# Power.net
KiCad netlist of a schematic drawn in Altium Designer
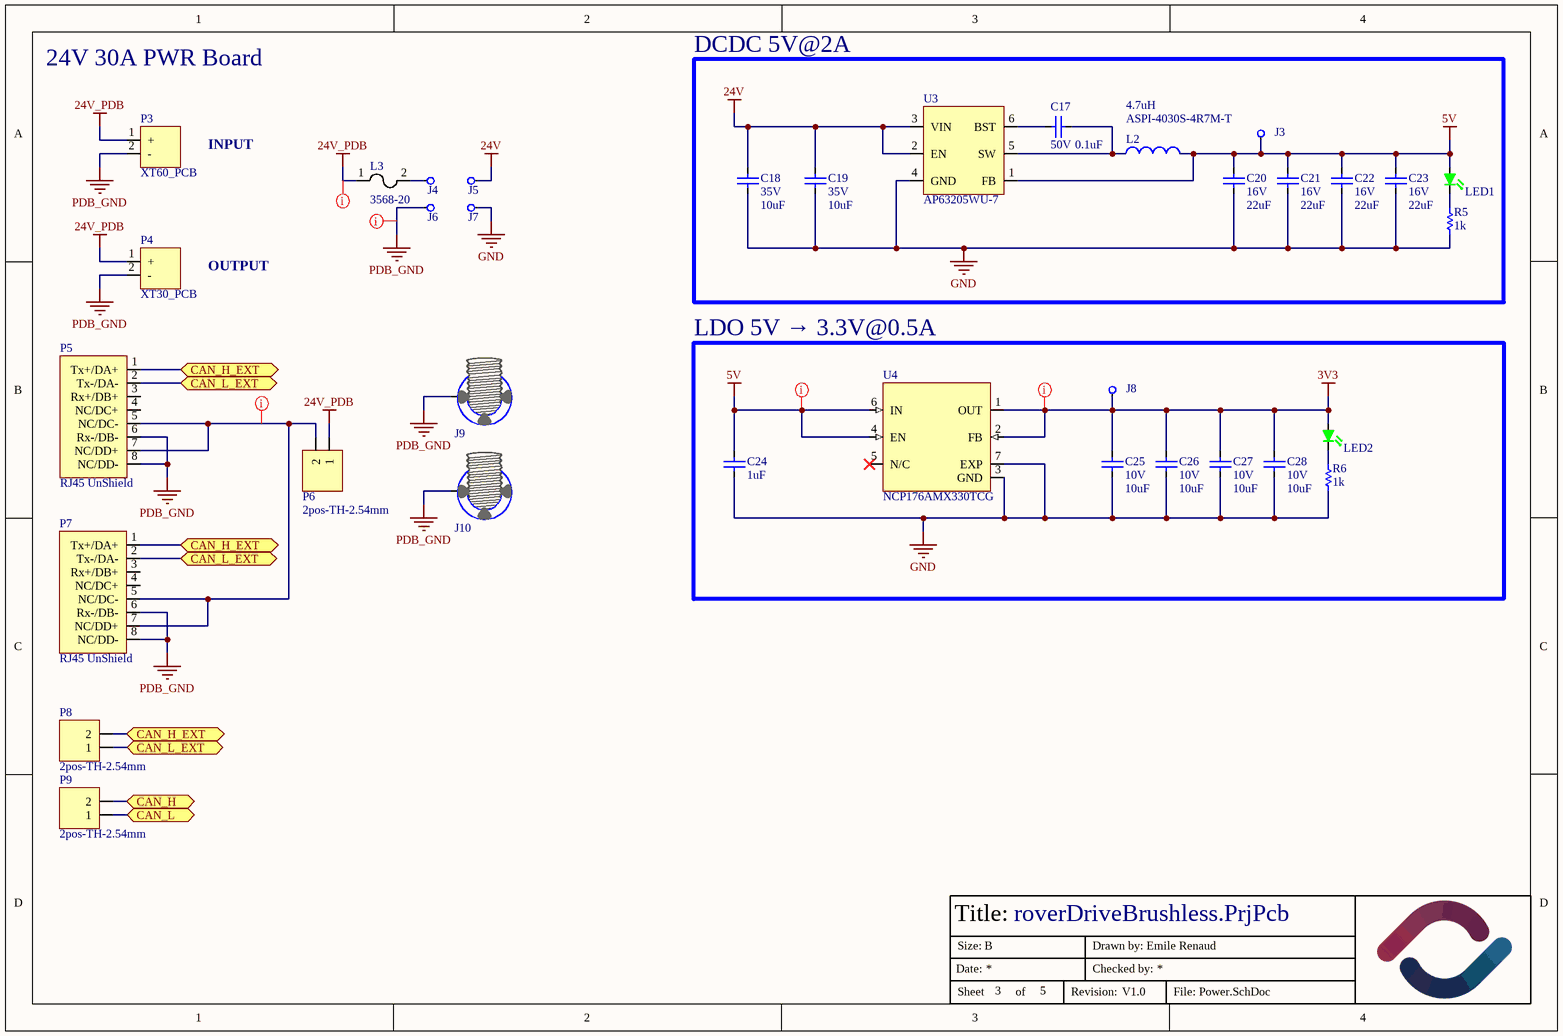
[diagram p0: Power.SchDoc]

(export (version "E")
  (design (tool "Eeschema 10.0.6"))
  (components
    (comp (ref "C17")
      (value "0.1uF")
      (footprint "CAPACITOR-0603")
      (description "Capacitor-0603-0.1uF-50V-X7R")
      (fields (field (name "VOLT") "50V"))
      (libsource (lib "Capacitors") (part "Capacitor-0603-0.1uF-50V-X7R"))
    )
    (comp (ref "C18")
      (value "10uF")
      (footprint "CAPACITOR-0805")
      (description "Capacitor-0805-10uF-35V-X5R")
      (fields (field (name "VOLT") "35V"))
      (libsource (lib "Capacitors") (part "Capacitor-0805-10uF-35V-X5R"))
    )
    (comp (ref "C19")
      (value "10uF")
      (footprint "CAPACITOR-0805")
      (description "Capacitor-0805-10uF-35V-X5R")
      (fields (field (name "VOLT") "35V"))
      (libsource (lib "Capacitors") (part "Capacitor-0805-10uF-35V-X5R"))
    )
    (comp (ref "C20")
      (value "22uF")
      (footprint "CAPACITOR-0805")
      (description "Capacitor-0805-22uF-16V-X5R")
      (fields (field (name "VOLT") "16V"))
      (libsource (lib "Capacitors") (part "Capacitor-0805-22uF-16V-X5R"))
    )
    (comp (ref "C21")
      (value "22uF")
      (footprint "CAPACITOR-0805")
      (description "Capacitor-0805-22uF-16V-X5R")
      (fields (field (name "VOLT") "16V"))
      (libsource (lib "Capacitors") (part "Capacitor-0805-22uF-16V-X5R"))
    )
    (comp (ref "C22")
      (value "22uF")
      (footprint "CAPACITOR-0805")
      (description "Capacitor-0805-22uF-16V-X5R")
      (fields (field (name "VOLT") "16V"))
      (libsource (lib "Capacitors") (part "Capacitor-0805-22uF-16V-X5R"))
    )
    (comp (ref "C23")
      (value "22uF")
      (footprint "CAPACITOR-0805")
      (description "Capacitor-0805-22uF-16V-X5R")
      (fields (field (name "VOLT") "16V"))
      (libsource (lib "Capacitors") (part "Capacitor-0805-22uF-16V-X5R"))
    )
    (comp (ref "C24")
      (value "1uF")
      (footprint "CAPACITOR-0603")
      (description "Capacitor-0603-1uF-25V-X5R")
      (libsource (lib "Capacitors") (part "Capacitor-0603-1uF-25V-X5R"))
    )
    (comp (ref "C25")
      (value "10uF")
      (footprint "CAPACITOR-0603")
      (description "10 µF ±20% 10V Ceramic Capacitor X5R 0603 (1608 Metric)")
      (fields (field (name "VOLT") "10V") (field (name "Comment") "Capacitor-0603-10uF-10V-X5R"))
      (libsource (lib "Capacitors") (part "Capacitor-0603-10uF-10V-X5R"))
    )
    (comp (ref "C26")
      (value "10uF")
      (footprint "CAPACITOR-0603")
      (description "10 µF ±20% 10V Ceramic Capacitor X5R 0603 (1608 Metric)")
      (fields (field (name "VOLT") "10V") (field (name "Comment") "Capacitor-0603-10uF-10V-X5R"))
      (libsource (lib "Capacitors") (part "Capacitor-0603-10uF-10V-X5R"))
    )
    (comp (ref "C27")
      (value "10uF")
      (footprint "CAPACITOR-0603")
      (description "10 µF ±20% 10V Ceramic Capacitor X5R 0603 (1608 Metric)")
      (fields (field (name "VOLT") "10V") (field (name "Comment") "Capacitor-0603-10uF-10V-X5R"))
      (libsource (lib "Capacitors") (part "Capacitor-0603-10uF-10V-X5R"))
    )
    (comp (ref "C28")
      (value "10uF")
      (footprint "CAPACITOR-0603")
      (description "10 µF ±20% 10V Ceramic Capacitor X5R 0603 (1608 Metric)")
      (fields (field (name "VOLT") "10V") (field (name "Comment") "Capacitor-0603-10uF-10V-X5R"))
      (libsource (lib "Capacitors") (part "Capacitor-0603-10uF-10V-X5R"))
    )
    (comp (ref "J3")
      (value "hole")
      (footprint "PAD-1.2MM-silk")
      (libsource (lib "JumpersAndHoles") (part "PAD 1.2mm"))
    )
    (comp (ref "J4")
      (value "hole")
      (footprint "HOLE-2.70MM")
      (description "Hole for 12 AWG Stranded Wire")
      (libsource (lib "JumpersAndHoles") (part "Hole 2.70mm AWG12-Stranded"))
    )
    (comp (ref "J5")
      (value "hole")
      (footprint "HOLE-2.70MM")
      (description "Hole for 12 AWG Stranded Wire")
      (libsource (lib "JumpersAndHoles") (part "Hole 2.70mm AWG12-Stranded"))
    )
    (comp (ref "J6")
      (value "hole")
      (footprint "HOLE-2.70MM")
      (description "Hole for 12 AWG Stranded Wire")
      (libsource (lib "JumpersAndHoles") (part "Hole 2.70mm AWG12-Stranded"))
    )
    (comp (ref "J7")
      (value "hole")
      (footprint "HOLE-2.70MM")
      (description "Hole for 12 AWG Stranded Wire")
      (libsource (lib "JumpersAndHoles") (part "Hole 2.70mm AWG12-Stranded"))
    )
    (comp (ref "J8")
      (value "hole")
      (footprint "PAD-1.2MM-silk")
      (libsource (lib "JumpersAndHoles") (part "PAD 1.2mm"))
    )
    (comp (ref "J9")
      (value "hole")
      (footprint "HOLE-3.40MM-M3-7MMEYELET-MountingFeature")
      (description "Hole for M3 Bolt with 7mm pad")
      (libsource (lib "JumpersAndHoles") (part "Hole 3.40mm M3-MountingFeature"))
    )
    (comp (ref "J10")
      (value "hole")
      (footprint "HOLE-3.40MM-M3-7MMEYELET-MountingFeature")
      (description "Hole for M3 Bolt with 7mm pad")
      (libsource (lib "JumpersAndHoles") (part "Hole 3.40mm M3-MountingFeature"))
    )
    (comp (ref "L2")
      (value "ASPI-4030S-4R7M-T")
      (footprint "INDUCTOR_ASPI-4030S-100M")
      (description "4.7 µH Shielded Drum Core, Wirewound Inductor 2 A 60mOhm Nonstandard")
      (fields (field (name "ALTIUM_VALUE") "4.7uH"))
      (libsource (lib "Inductors") (part "ASPI-4030S-4R7M-T"))
    )
    (comp (ref "L3")
      (value "3568-20")
      (footprint "FUSE_3568-20")
      (description "Fuse Holder 30 A 500V 1 Circuit Blade Through Hole")
      (libsource (lib "Fuses") (part "3568-20"))
    )
    (comp (ref "LED1")
      (value "3147-B1911NG--20D000214U1930CT-ND")
      (footprint "LED-0603-2PIN-SILKSCREEN")
      (description "LED GREEN DIFFUSED 0603 SMD")
      (libsource (lib "LEDs") (part "LED_GREEN"))
    )
    (comp (ref "LED2")
      (value "3147-B1911NG--20D000214U1930CT-ND")
      (footprint "LED-0603-2PIN-SILKSCREEN")
      (description "LED GREEN DIFFUSED 0603 SMD")
      (libsource (lib "LEDs") (part "LED_GREEN"))
    )
    (comp (ref "P3")
      (value "XT60_PCB")
      (footprint "XT60PW-M")
      (description "XT60")
      (libsource (lib "BatteriesConnector") (part "XT60_pcb"))
    )
    (comp (ref "P4")
      (value "XT30_PCB")
      (footprint "XT30PW_smd")
      (description "XT30")
      (libsource (lib "BatteriesConnector") (part "XT30_pcb"))
    )
    (comp (ref "P5")
      (value "RJ45 UnShield")
      (footprint "AMPHENOL_54602-908LF")
      (description "Jack Modular Connector 8p8c (RJ45, Ethernet) 90° Angle (Right) Unshielded Cat3")
      (libsource (lib "PC-connector") (part "RJ545"))
    )
    (comp (ref "P6")
      (value "2pos-TH-2.54mm")
      (footprint "HDR1X2")
      (description "2pos TH 2.54mm Header")
      (libsource (lib "") (part "2pos-TH-2.54mm_1"))
    )
    (comp (ref "P7")
      (value "RJ45 UnShield")
      (footprint "AMPHENOL_54602-908LF")
      (description "Jack Modular Connector 8p8c (RJ45, Ethernet) 90° Angle (Right) Unshielded Cat3")
      (libsource (lib "PC-connector") (part "RJ545"))
    )
    (comp (ref "P8")
      (value "2pos-TH-2.54mm")
      (footprint "HDR1X2")
      (description "2pos TH 2.54mm Header")
      (libsource (lib "Header") (part "2pos-TH-2.54mm"))
    )
    (comp (ref "P9")
      (value "2pos-TH-2.54mm")
      (footprint "HDR1X2")
      (description "2pos TH 2.54mm Header")
      (libsource (lib "Header") (part "2pos-TH-2.54mm"))
    )
    (comp (ref "R5")
      (value "1k")
      (footprint "Resistor-0603")
      (description "Resistor0603-1k")
      (fields (field (name "Comment") "SMT resistor"))
      (libsource (lib "Resistors") (part "Resistor0603-1k"))
    )
    (comp (ref "R6")
      (value "1k")
      (footprint "Resistor-0603")
      (description "Resistor0603-1k")
      (fields (field (name "Comment") "SMT resistor"))
      (libsource (lib "Resistors") (part "Resistor0603-1k"))
    )
    (comp (ref "U3")
      (value "AP63205WU-7")
      (footprint "SOT-23-6")
      (description "Fixed 5V@2A. 32V Input. SOT-23-6")
      (libsource (lib "PMIC-VoltageRegulators-DCDCSwitchingRegulators") (part "AP63205WU-7"))
    )
    (comp (ref "U4")
      (value "NCP176AMX330TCG")
      (footprint "PCB_Footprints:XFDFN-6 Exposed Pad")
      (description "IC REG LINEAR 3.3V 500mA 6-XDFN")
      (libsource (lib "PMIC-VoltageRegulators-LinearRegulators") (part "NCP176AMX330TCG"))
    )
  )
  (nets
    (net (code "1") (name "/CAN_H") (class "Default")
      (node (ref "P9") (pin "2") (pinfunction "2_2") (pintype "passive"))
    )
    (net (code "2") (name "/CAN_H_EXT") (class "Default")
      (node (ref "P5") (pin "1") (pinfunction "Tx+/DA+_1") (pintype "passive"))
      (node (ref "P7") (pin "1") (pinfunction "Tx+/DA+_1") (pintype "passive"))
      (node (ref "P8") (pin "2") (pinfunction "2_2") (pintype "passive"))
    )
    (net (code "3") (name "/CAN_L") (class "Default")
      (node (ref "P9") (pin "1") (pinfunction "1_1") (pintype "passive"))
    )
    (net (code "4") (name "/CAN_L_EXT") (class "Default")
      (node (ref "P5") (pin "2") (pinfunction "Tx-/DA-_2") (pintype "passive"))
      (node (ref "P7") (pin "2") (pinfunction "Tx-/DA-_2") (pintype "passive"))
      (node (ref "P8") (pin "1") (pinfunction "1_1") (pintype "passive"))
    )
    (net (code "5") (name "3V3") (class "Default")
      (node (ref "C25") (pin "2") (pinfunction "2_2") (pintype "passive"))
      (node (ref "C26") (pin "2") (pinfunction "2_2") (pintype "passive"))
      (node (ref "C27") (pin "2") (pinfunction "2_2") (pintype "passive"))
      (node (ref "C28") (pin "2") (pinfunction "2_2") (pintype "passive"))
      (node (ref "J8") (pin "1") (pinfunction "1_1") (pintype "passive"))
      (node (ref "LED2") (pin "2") (pinfunction "R_2") (pintype "passive"))
      (node (ref "U4") (pin "1") (pinfunction "OUT_1") (pintype "passive"))
      (node (ref "U4") (pin "2") (pinfunction "FB_2") (pintype "input"))
    )
    (net (code "6") (name "5V") (class "Default")
      (node (ref "C20") (pin "2") (pinfunction "2_2") (pintype "passive"))
      (node (ref "C21") (pin "2") (pinfunction "2_2") (pintype "passive"))
      (node (ref "C22") (pin "2") (pinfunction "2_2") (pintype "passive"))
      (node (ref "C23") (pin "2") (pinfunction "2_2") (pintype "passive"))
      (node (ref "C24") (pin "2") (pinfunction "2_2") (pintype "passive"))
      (node (ref "J3") (pin "1") (pinfunction "1_1") (pintype "passive"))
      (node (ref "L2") (pin "2") (pinfunction "2_2") (pintype "passive"))
      (node (ref "LED1") (pin "2") (pinfunction "R_2") (pintype "passive"))
      (node (ref "U3") (pin "1") (pinfunction "FB_1") (pintype "passive"))
      (node (ref "U4") (pin "4") (pinfunction "EN_4") (pintype "input"))
      (node (ref "U4") (pin "6") (pinfunction "IN_6") (pintype "input"))
    )
    (net (code "7") (name "24V") (class "Default")
      (node (ref "C18") (pin "2") (pinfunction "2_2") (pintype "passive"))
      (node (ref "C19") (pin "2") (pinfunction "2_2") (pintype "passive"))
      (node (ref "J5") (pin "1") (pinfunction "1_1") (pintype "passive"))
      (node (ref "U3") (pin "2") (pinfunction "EN_2") (pintype "passive"))
      (node (ref "U3") (pin "3") (pinfunction "VIN_3") (pintype "passive"))
    )
    (net (code "8") (name "24V_PDB") (class "Default")
      (node (ref "L3") (pin "1") (pinfunction "1_1") (pintype "passive"))
      (node (ref "P3") (pin "1") (pinfunction "+_1") (pintype "passive"))
      (node (ref "P4") (pin "1") (pinfunction "+_1") (pintype "passive"))
      (node (ref "P6") (pin "1") (pinfunction "1_1") (pintype "passive"))
    )
    (net (code "9") (name "GND") (class "Default")
      (node (ref "C18") (pin "1") (pinfunction "1_1") (pintype "passive"))
      (node (ref "C19") (pin "1") (pinfunction "1_1") (pintype "passive"))
      (node (ref "C20") (pin "1") (pinfunction "1_1") (pintype "passive"))
      (node (ref "C21") (pin "1") (pinfunction "1_1") (pintype "passive"))
      (node (ref "C22") (pin "1") (pinfunction "1_1") (pintype "passive"))
      (node (ref "C23") (pin "1") (pinfunction "1_1") (pintype "passive"))
      (node (ref "C24") (pin "1") (pinfunction "1_1") (pintype "passive"))
      (node (ref "C25") (pin "1") (pinfunction "1_1") (pintype "passive"))
      (node (ref "C26") (pin "1") (pinfunction "1_1") (pintype "passive"))
      (node (ref "C27") (pin "1") (pinfunction "1_1") (pintype "passive"))
      (node (ref "C28") (pin "1") (pinfunction "1_1") (pintype "passive"))
      (node (ref "J7") (pin "1") (pinfunction "1_1") (pintype "passive"))
      (node (ref "R5") (pin "1") (pinfunction "1_1") (pintype "passive"))
      (node (ref "R6") (pin "1") (pinfunction "1_1") (pintype "passive"))
      (node (ref "U3") (pin "4") (pinfunction "GND_4") (pintype "passive"))
      (node (ref "U4") (pin "3") (pinfunction "GND_3") (pintype "power_in"))
      (node (ref "U4") (pin "7") (pinfunction "EXP_7") (pintype "power_in"))
    )
    (net (code "10") (name "Net-(J4-Pad1)") (class "Default")
      (node (ref "J4") (pin "1") (pinfunction "1_1") (pintype "passive"))
      (node (ref "L3") (pin "2") (pinfunction "2_2") (pintype "passive"))
    )
    (net (code "11") (name "Net-(LED1-K)") (class "Default")
      (node (ref "LED1") (pin "1") (pinfunction "K_1") (pintype "passive"))
      (node (ref "R5") (pin "2") (pinfunction "2_2") (pintype "passive"))
    )
    (net (code "12") (name "Net-(LED2-K)") (class "Default")
      (node (ref "LED2") (pin "1") (pinfunction "K_1") (pintype "passive"))
      (node (ref "R6") (pin "2") (pinfunction "2_2") (pintype "passive"))
    )
    (net (code "13") (name "Net-(P5-NC{slash}DC-)") (class "Default")
      (node (ref "P5") (pin "5") (pinfunction "NC/DC-_5") (pintype "passive"))
      (node (ref "P5") (pin "7") (pinfunction "NC/DD+_7") (pintype "passive"))
      (node (ref "P6") (pin "2") (pinfunction "2_2") (pintype "passive"))
      (node (ref "P7") (pin "5") (pinfunction "NC/DC-_5") (pintype "passive"))
      (node (ref "P7") (pin "7") (pinfunction "NC/DD+_7") (pintype "passive"))
    )
    (net (code "14") (name "Net-(U3-BST)") (class "Default")
      (node (ref "C17") (pin "1") (pinfunction "1_1") (pintype "passive"))
      (node (ref "U3") (pin "6") (pinfunction "BST_6") (pintype "passive"))
    )
    (net (code "15") (name "Net-(U3-SW)") (class "Default")
      (node (ref "C17") (pin "2") (pinfunction "2_2") (pintype "passive"))
      (node (ref "L2") (pin "1") (pinfunction "1_1") (pintype "passive"))
      (node (ref "U3") (pin "5") (pinfunction "SW_5") (pintype "passive"))
    )
    (net (code "16") (name "PDB_GND") (class "Default")
      (node (ref "J10") (pin "1") (pinfunction "1_1") (pintype "passive"))
      (node (ref "J6") (pin "1") (pinfunction "1_1") (pintype "passive"))
      (node (ref "J9") (pin "1") (pinfunction "1_1") (pintype "passive"))
      (node (ref "P3") (pin "2") (pinfunction "-_2") (pintype "passive"))
      (node (ref "P4") (pin "2") (pinfunction "-_2") (pintype "passive"))
      (node (ref "P5") (pin "6") (pinfunction "Rx-/DB-_6") (pintype "passive"))
      (node (ref "P5") (pin "8") (pinfunction "NC/DD-_8") (pintype "passive"))
      (node (ref "P7") (pin "6") (pinfunction "Rx-/DB-_6") (pintype "passive"))
      (node (ref "P7") (pin "8") (pinfunction "NC/DD-_8") (pintype "passive"))
    )
    (net (code "17") (name "unconnected-(P5-NC{slash}DC+-Pad4)") (class "Default")
      (node (ref "P5") (pin "4") (pinfunction "NC/DC+_4") (pintype "passive"))
    )
    (net (code "18") (name "unconnected-(P5-Rx+{slash}DB+-Pad3)") (class "Default")
      (node (ref "P5") (pin "3") (pinfunction "Rx+/DB+_3") (pintype "passive"))
    )
    (net (code "19") (name "unconnected-(P7-NC{slash}DC+-Pad4)") (class "Default")
      (node (ref "P7") (pin "4") (pinfunction "NC/DC+_4") (pintype "passive"))
    )
    (net (code "20") (name "unconnected-(P7-Rx+{slash}DB+-Pad3)") (class "Default")
      (node (ref "P7") (pin "3") (pinfunction "Rx+/DB+_3") (pintype "passive"))
    )
    (net (code "21") (name "unconnected-(U4-N{slash}C-Pad5)") (class "Default")
      (node (ref "U4") (pin "5") (pinfunction "N/C_5") (pintype "passive+no_connect"))
    )
  )
)
